# Sheet_1_2024-08-25.net
KiCad netlist of a schematic drawn in Altium Designer
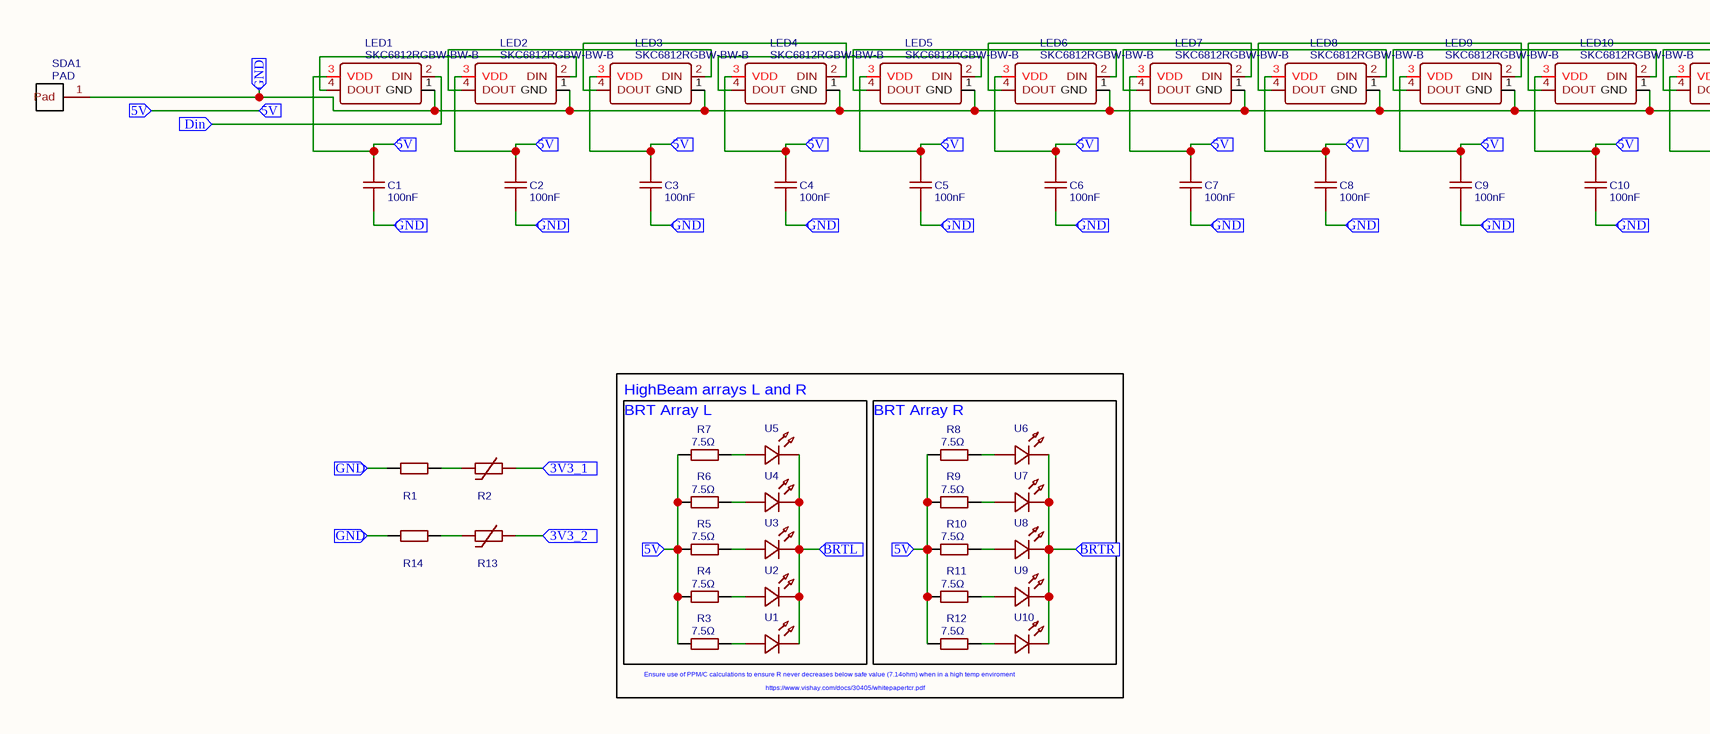
[diagram p0: Sheet_1_2024-08-25.schdoc, left]
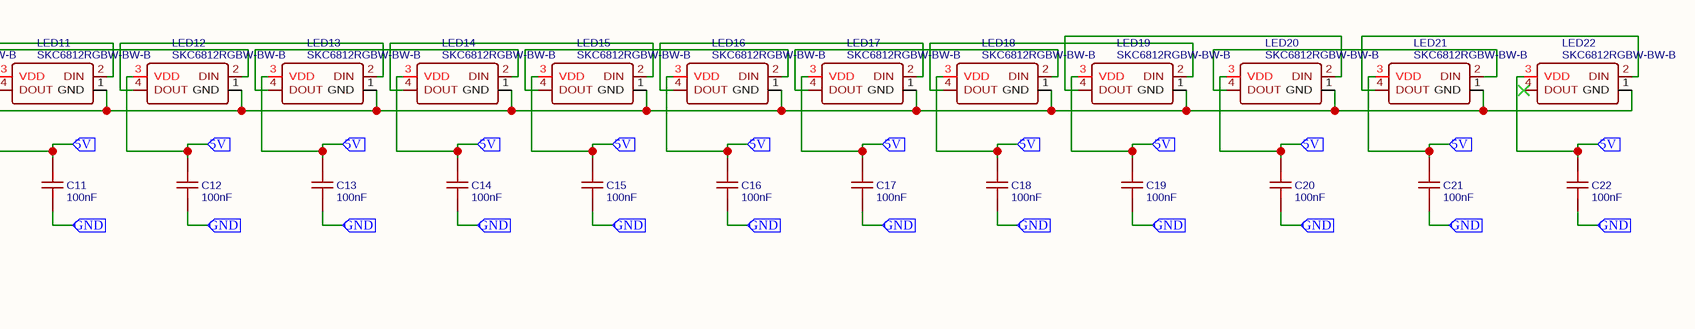
[diagram p1: Sheet_1_2024-08-25.schdoc, right]

(export (version "E")
  (design (tool "Eeschema 10.0.6"))
  (components
    (comp (ref "C1")
      (value "100nF")
      (fields
        (field (name "MANUFACTURER") "YAGEO(国巨)")
        (field (name "MANUFACTURER PART") "CC0402KRX7R6BB104")
        (field (name "CONTRIBUTOR") "LCSC")
      )
      (libsource (lib "altium-import") (part "root_0_100nF_"))
    )
    (comp (ref "C2")
      (value "100nF")
      (fields
        (field (name "MANUFACTURER") "YAGEO(国巨)")
        (field (name "MANUFACTURER PART") "CC0402KRX7R6BB104")
        (field (name "CONTRIBUTOR") "LCSC")
      )
      (libsource (lib "altium-import") (part "root_0_100nF_"))
    )
    (comp (ref "C3")
      (value "100nF")
      (fields
        (field (name "MANUFACTURER") "YAGEO(国巨)")
        (field (name "MANUFACTURER PART") "CC0402KRX7R6BB104")
        (field (name "CONTRIBUTOR") "LCSC")
      )
      (libsource (lib "altium-import") (part "root_0_100nF_"))
    )
    (comp (ref "C4")
      (value "100nF")
      (fields
        (field (name "MANUFACTURER") "YAGEO(国巨)")
        (field (name "MANUFACTURER PART") "CC0402KRX7R6BB104")
        (field (name "CONTRIBUTOR") "LCSC")
      )
      (libsource (lib "altium-import") (part "root_0_100nF_"))
    )
    (comp (ref "C5")
      (value "100nF")
      (fields
        (field (name "MANUFACTURER") "YAGEO(国巨)")
        (field (name "MANUFACTURER PART") "CC0402KRX7R6BB104")
        (field (name "CONTRIBUTOR") "LCSC")
      )
      (libsource (lib "altium-import") (part "root_0_100nF_"))
    )
    (comp (ref "C6")
      (value "100nF")
      (fields
        (field (name "MANUFACTURER") "YAGEO(国巨)")
        (field (name "MANUFACTURER PART") "CC0402KRX7R6BB104")
        (field (name "CONTRIBUTOR") "LCSC")
      )
      (libsource (lib "altium-import") (part "root_0_100nF_"))
    )
    (comp (ref "C7")
      (value "100nF")
      (fields
        (field (name "MANUFACTURER") "YAGEO(国巨)")
        (field (name "MANUFACTURER PART") "CC0402KRX7R6BB104")
        (field (name "CONTRIBUTOR") "LCSC")
      )
      (libsource (lib "altium-import") (part "root_0_100nF_"))
    )
    (comp (ref "C8")
      (value "100nF")
      (fields
        (field (name "MANUFACTURER") "YAGEO(国巨)")
        (field (name "MANUFACTURER PART") "CC0402KRX7R6BB104")
        (field (name "CONTRIBUTOR") "LCSC")
      )
      (libsource (lib "altium-import") (part "root_0_100nF_"))
    )
    (comp (ref "C9")
      (value "100nF")
      (fields
        (field (name "MANUFACTURER") "YAGEO(国巨)")
        (field (name "MANUFACTURER PART") "CC0402KRX7R6BB104")
        (field (name "CONTRIBUTOR") "LCSC")
      )
      (libsource (lib "altium-import") (part "root_0_100nF_"))
    )
    (comp (ref "C10")
      (value "100nF")
      (fields
        (field (name "MANUFACTURER") "YAGEO(国巨)")
        (field (name "MANUFACTURER PART") "CC0402KRX7R6BB104")
        (field (name "CONTRIBUTOR") "LCSC")
      )
      (libsource (lib "altium-import") (part "root_0_100nF_"))
    )
    (comp (ref "C11")
      (value "100nF")
      (fields
        (field (name "MANUFACTURER") "YAGEO(国巨)")
        (field (name "MANUFACTURER PART") "CC0402KRX7R6BB104")
        (field (name "CONTRIBUTOR") "LCSC")
      )
      (libsource (lib "altium-import") (part "root_0_100nF_"))
    )
    (comp (ref "C12")
      (value "100nF")
      (fields
        (field (name "MANUFACTURER") "YAGEO(国巨)")
        (field (name "MANUFACTURER PART") "CC0402KRX7R6BB104")
        (field (name "CONTRIBUTOR") "LCSC")
      )
      (libsource (lib "altium-import") (part "root_0_100nF_"))
    )
    (comp (ref "C13")
      (value "100nF")
      (fields
        (field (name "MANUFACTURER") "YAGEO(国巨)")
        (field (name "MANUFACTURER PART") "CC0402KRX7R6BB104")
        (field (name "CONTRIBUTOR") "LCSC")
      )
      (libsource (lib "altium-import") (part "root_0_100nF_"))
    )
    (comp (ref "C14")
      (value "100nF")
      (fields
        (field (name "MANUFACTURER") "YAGEO(国巨)")
        (field (name "MANUFACTURER PART") "CC0402KRX7R6BB104")
        (field (name "CONTRIBUTOR") "LCSC")
      )
      (libsource (lib "altium-import") (part "root_0_100nF_"))
    )
    (comp (ref "C15")
      (value "100nF")
      (fields
        (field (name "MANUFACTURER") "YAGEO(国巨)")
        (field (name "MANUFACTURER PART") "CC0402KRX7R6BB104")
        (field (name "CONTRIBUTOR") "LCSC")
      )
      (libsource (lib "altium-import") (part "root_0_100nF_"))
    )
    (comp (ref "C16")
      (value "100nF")
      (fields
        (field (name "MANUFACTURER") "YAGEO(国巨)")
        (field (name "MANUFACTURER PART") "CC0402KRX7R6BB104")
        (field (name "CONTRIBUTOR") "LCSC")
      )
      (libsource (lib "altium-import") (part "root_0_100nF_"))
    )
    (comp (ref "C17")
      (value "100nF")
      (fields
        (field (name "MANUFACTURER") "YAGEO(国巨)")
        (field (name "MANUFACTURER PART") "CC0402KRX7R6BB104")
        (field (name "CONTRIBUTOR") "LCSC")
      )
      (libsource (lib "altium-import") (part "root_0_100nF_"))
    )
    (comp (ref "C18")
      (value "100nF")
      (fields
        (field (name "MANUFACTURER") "YAGEO(国巨)")
        (field (name "MANUFACTURER PART") "CC0402KRX7R6BB104")
        (field (name "CONTRIBUTOR") "LCSC")
      )
      (libsource (lib "altium-import") (part "root_0_100nF_"))
    )
    (comp (ref "C19")
      (value "100nF")
      (fields
        (field (name "MANUFACTURER") "YAGEO(国巨)")
        (field (name "MANUFACTURER PART") "CC0402KRX7R6BB104")
        (field (name "CONTRIBUTOR") "LCSC")
      )
      (libsource (lib "altium-import") (part "root_0_100nF_"))
    )
    (comp (ref "C20")
      (value "100nF")
      (fields
        (field (name "MANUFACTURER") "YAGEO(国巨)")
        (field (name "MANUFACTURER PART") "CC0402KRX7R6BB104")
        (field (name "CONTRIBUTOR") "LCSC")
      )
      (libsource (lib "altium-import") (part "root_0_100nF_"))
    )
    (comp (ref "C21")
      (value "100nF")
      (fields
        (field (name "MANUFACTURER") "YAGEO(国巨)")
        (field (name "MANUFACTURER PART") "CC0402KRX7R6BB104")
        (field (name "CONTRIBUTOR") "LCSC")
      )
      (libsource (lib "altium-import") (part "root_0_100nF_"))
    )
    (comp (ref "C22")
      (value "100nF")
      (fields
        (field (name "MANUFACTURER") "YAGEO(国巨)")
        (field (name "MANUFACTURER PART") "CC0402KRX7R6BB104")
        (field (name "CONTRIBUTOR") "LCSC")
      )
      (libsource (lib "altium-import") (part "root_0_100nF_"))
    )
    (comp (ref "LED1")
      (value "SKC6812RGBW-BW-B")
      (fields (field (name "MANUFACTURER") "欧思科光电") (field (name "CONTRIBUTOR") "lcsc"))
      (libsource (lib "altium-import") (part "root_0_SKC6812RGBW-BW-B_"))
    )
    (comp (ref "LED2")
      (value "SKC6812RGBW-BW-B")
      (fields (field (name "MANUFACTURER") "欧思科光电") (field (name "CONTRIBUTOR") "lcsc"))
      (libsource (lib "altium-import") (part "root_0_SKC6812RGBW-BW-B_"))
    )
    (comp (ref "LED3")
      (value "SKC6812RGBW-BW-B")
      (fields (field (name "MANUFACTURER") "欧思科光电") (field (name "CONTRIBUTOR") "lcsc"))
      (libsource (lib "altium-import") (part "root_0_SKC6812RGBW-BW-B_"))
    )
    (comp (ref "LED4")
      (value "SKC6812RGBW-BW-B")
      (fields (field (name "MANUFACTURER") "欧思科光电") (field (name "CONTRIBUTOR") "lcsc"))
      (libsource (lib "altium-import") (part "root_0_SKC6812RGBW-BW-B_"))
    )
    (comp (ref "LED5")
      (value "SKC6812RGBW-BW-B")
      (fields (field (name "MANUFACTURER") "欧思科光电") (field (name "CONTRIBUTOR") "lcsc"))
      (libsource (lib "altium-import") (part "root_0_SKC6812RGBW-BW-B_"))
    )
    (comp (ref "LED6")
      (value "SKC6812RGBW-BW-B")
      (fields (field (name "MANUFACTURER") "欧思科光电") (field (name "CONTRIBUTOR") "lcsc"))
      (libsource (lib "altium-import") (part "root_0_SKC6812RGBW-BW-B_"))
    )
    (comp (ref "LED7")
      (value "SKC6812RGBW-BW-B")
      (fields (field (name "MANUFACTURER") "欧思科光电") (field (name "CONTRIBUTOR") "lcsc"))
      (libsource (lib "altium-import") (part "root_0_SKC6812RGBW-BW-B_"))
    )
    (comp (ref "LED8")
      (value "SKC6812RGBW-BW-B")
      (fields (field (name "MANUFACTURER") "欧思科光电") (field (name "CONTRIBUTOR") "lcsc"))
      (libsource (lib "altium-import") (part "root_0_SKC6812RGBW-BW-B_"))
    )
    (comp (ref "LED9")
      (value "SKC6812RGBW-BW-B")
      (fields (field (name "MANUFACTURER") "欧思科光电") (field (name "CONTRIBUTOR") "lcsc"))
      (libsource (lib "altium-import") (part "root_0_SKC6812RGBW-BW-B_"))
    )
    (comp (ref "LED10")
      (value "SKC6812RGBW-BW-B")
      (fields (field (name "MANUFACTURER") "欧思科光电") (field (name "CONTRIBUTOR") "lcsc"))
      (libsource (lib "altium-import") (part "root_0_SKC6812RGBW-BW-B_"))
    )
    (comp (ref "LED11")
      (value "SKC6812RGBW-BW-B")
      (fields (field (name "MANUFACTURER") "欧思科光电") (field (name "CONTRIBUTOR") "lcsc"))
      (libsource (lib "altium-import") (part "root_0_SKC6812RGBW-BW-B_"))
    )
    (comp (ref "LED12")
      (value "SKC6812RGBW-BW-B")
      (fields (field (name "MANUFACTURER") "欧思科光电") (field (name "CONTRIBUTOR") "lcsc"))
      (libsource (lib "altium-import") (part "root_0_SKC6812RGBW-BW-B_"))
    )
    (comp (ref "LED13")
      (value "SKC6812RGBW-BW-B")
      (fields (field (name "MANUFACTURER") "欧思科光电") (field (name "CONTRIBUTOR") "lcsc"))
      (libsource (lib "altium-import") (part "root_0_SKC6812RGBW-BW-B_"))
    )
    (comp (ref "LED14")
      (value "SKC6812RGBW-BW-B")
      (fields (field (name "MANUFACTURER") "欧思科光电") (field (name "CONTRIBUTOR") "lcsc"))
      (libsource (lib "altium-import") (part "root_0_SKC6812RGBW-BW-B_"))
    )
    (comp (ref "LED15")
      (value "SKC6812RGBW-BW-B")
      (fields (field (name "MANUFACTURER") "欧思科光电") (field (name "CONTRIBUTOR") "lcsc"))
      (libsource (lib "altium-import") (part "root_0_SKC6812RGBW-BW-B_"))
    )
    (comp (ref "LED16")
      (value "SKC6812RGBW-BW-B")
      (fields (field (name "MANUFACTURER") "欧思科光电") (field (name "CONTRIBUTOR") "lcsc"))
      (libsource (lib "altium-import") (part "root_0_SKC6812RGBW-BW-B_"))
    )
    (comp (ref "LED17")
      (value "SKC6812RGBW-BW-B")
      (fields (field (name "MANUFACTURER") "欧思科光电") (field (name "CONTRIBUTOR") "lcsc"))
      (libsource (lib "altium-import") (part "root_0_SKC6812RGBW-BW-B_"))
    )
    (comp (ref "LED18")
      (value "SKC6812RGBW-BW-B")
      (fields (field (name "MANUFACTURER") "欧思科光电") (field (name "CONTRIBUTOR") "lcsc"))
      (libsource (lib "altium-import") (part "root_0_SKC6812RGBW-BW-B_"))
    )
    (comp (ref "LED19")
      (value "SKC6812RGBW-BW-B")
      (fields (field (name "MANUFACTURER") "欧思科光电") (field (name "CONTRIBUTOR") "lcsc"))
      (libsource (lib "altium-import") (part "root_0_SKC6812RGBW-BW-B_"))
    )
    (comp (ref "LED20")
      (value "SKC6812RGBW-BW-B")
      (fields (field (name "MANUFACTURER") "欧思科光电") (field (name "CONTRIBUTOR") "lcsc"))
      (libsource (lib "altium-import") (part "root_0_SKC6812RGBW-BW-B_"))
    )
    (comp (ref "LED21")
      (value "SKC6812RGBW-BW-B")
      (fields (field (name "MANUFACTURER") "欧思科光电") (field (name "CONTRIBUTOR") "lcsc"))
      (libsource (lib "altium-import") (part "root_0_SKC6812RGBW-BW-B_"))
    )
    (comp (ref "LED22")
      (value "SKC6812RGBW-BW-B")
      (fields (field (name "MANUFACTURER") "欧思科光电") (field (name "CONTRIBUTOR") "lcsc"))
      (libsource (lib "altium-import") (part "root_0_SKC6812RGBW-BW-B_"))
    )
    (comp (ref "R1")
      (value "100kΩ")
      (fields
        (field (name "MANUFACTURER") "UNI-ROYAL(厚声)")
        (field (name "MANUFACTURER PART") "0603WAF1003T5E")
      )
      (libsource (lib "altium-import") (part "root_0_100kΩ_"))
    )
    (comp (ref "R2")
      (value "SDNT1608X104F3950FTF")
      (fields (field (name "MANUFACTURER") "Sunlord(顺络)") (field (name "CONTRIBUTOR") "lcsc"))
      (libsource (lib "altium-import") (part "root_0_SDNT1608X104F3950FTF_"))
    )
    (comp (ref "R3")
      (value "7.5Ω")
      (fields
        (field (name "MANUFACTURER") "UNI-ROYAL(厚声)")
        (field (name "MANUFACTURER PART") "25121WF750KT4E")
      )
      (libsource (lib "altium-import") (part "root_0_7.5Ω_"))
    )
    (comp (ref "R4")
      (value "7.5Ω")
      (fields
        (field (name "MANUFACTURER") "UNI-ROYAL(厚声)")
        (field (name "MANUFACTURER PART") "25121WF750KT4E")
      )
      (libsource (lib "altium-import") (part "root_0_7.5Ω_"))
    )
    (comp (ref "R5")
      (value "7.5Ω")
      (fields
        (field (name "MANUFACTURER") "UNI-ROYAL(厚声)")
        (field (name "MANUFACTURER PART") "25121WF750KT4E")
      )
      (libsource (lib "altium-import") (part "root_0_7.5Ω_"))
    )
    (comp (ref "R6")
      (value "7.5Ω")
      (fields
        (field (name "MANUFACTURER") "UNI-ROYAL(厚声)")
        (field (name "MANUFACTURER PART") "25121WF750KT4E")
      )
      (libsource (lib "altium-import") (part "root_0_7.5Ω_"))
    )
    (comp (ref "R7")
      (value "7.5Ω")
      (fields
        (field (name "MANUFACTURER") "UNI-ROYAL(厚声)")
        (field (name "MANUFACTURER PART") "25121WF750KT4E")
      )
      (libsource (lib "altium-import") (part "root_0_7.5Ω_"))
    )
    (comp (ref "R8")
      (value "7.5Ω")
      (fields
        (field (name "MANUFACTURER") "UNI-ROYAL(厚声)")
        (field (name "MANUFACTURER PART") "25121WF750KT4E")
      )
      (libsource (lib "altium-import") (part "root_0_7.5Ω_"))
    )
    (comp (ref "R9")
      (value "7.5Ω")
      (fields
        (field (name "MANUFACTURER") "UNI-ROYAL(厚声)")
        (field (name "MANUFACTURER PART") "25121WF750KT4E")
      )
      (libsource (lib "altium-import") (part "root_0_7.5Ω_"))
    )
    (comp (ref "R10")
      (value "7.5Ω")
      (fields
        (field (name "MANUFACTURER") "UNI-ROYAL(厚声)")
        (field (name "MANUFACTURER PART") "25121WF750KT4E")
      )
      (libsource (lib "altium-import") (part "root_0_7.5Ω_"))
    )
    (comp (ref "R11")
      (value "7.5Ω")
      (fields
        (field (name "MANUFACTURER") "UNI-ROYAL(厚声)")
        (field (name "MANUFACTURER PART") "25121WF750KT4E")
      )
      (libsource (lib "altium-import") (part "root_0_7.5Ω_"))
    )
    (comp (ref "R12")
      (value "7.5Ω")
      (fields
        (field (name "MANUFACTURER") "UNI-ROYAL(厚声)")
        (field (name "MANUFACTURER PART") "25121WF750KT4E")
      )
      (libsource (lib "altium-import") (part "root_0_7.5Ω_"))
    )
    (comp (ref "R13")
      (value "SDNT1608X104F3950FTF")
      (fields (field (name "MANUFACTURER") "Sunlord(顺络)") (field (name "CONTRIBUTOR") "lcsc"))
      (libsource (lib "altium-import") (part "root_0_SDNT1608X104F3950FTF_"))
    )
    (comp (ref "R14")
      (value "100kΩ")
      (fields
        (field (name "MANUFACTURER") "UNI-ROYAL(厚声)")
        (field (name "MANUFACTURER PART") "0603WAF1003T5E")
      )
      (libsource (lib "altium-import") (part "root_0_100kΩ_"))
    )
    (comp (ref "SDA1")
      (value "PAD")
      (fields (field (name "CONTRIBUTOR") "edwardkeate"))
      (libsource (lib "altium-import") (part "root_0_PAD_"))
    )
    (comp (ref "U1")
      (value "JNJ-LTJH0111W60/26MIL/8000-9000K")
      (fields
        (field (name "MANUFACTURER") "JNJ OPTOELECTRONICS(强生光电)")
        (field (name "MANUFACTURER PART") "JNJ-LTJH0111W60/26mil/8000-9000K")
        (field (name "CONTRIBUTOR") "lcsc")
      )
      (libsource (lib "altium-import") (part "root_0_JNJ-LTJH0111W60/26MIL/8000-9000K_"))
    )
    (comp (ref "U2")
      (value "JNJ-LTJH0111W60/26MIL/8000-9000K")
      (fields
        (field (name "MANUFACTURER") "JNJ OPTOELECTRONICS(强生光电)")
        (field (name "MANUFACTURER PART") "JNJ-LTJH0111W60/26mil/8000-9000K")
        (field (name "CONTRIBUTOR") "lcsc")
      )
      (libsource (lib "altium-import") (part "root_0_JNJ-LTJH0111W60/26MIL/8000-9000K_"))
    )
    (comp (ref "U3")
      (value "JNJ-LTJH0111W60/26MIL/8000-9000K")
      (fields
        (field (name "MANUFACTURER") "JNJ OPTOELECTRONICS(强生光电)")
        (field (name "MANUFACTURER PART") "JNJ-LTJH0111W60/26mil/8000-9000K")
        (field (name "CONTRIBUTOR") "lcsc")
      )
      (libsource (lib "altium-import") (part "root_0_JNJ-LTJH0111W60/26MIL/8000-9000K_"))
    )
    (comp (ref "U4")
      (value "JNJ-LTJH0111W60/26MIL/8000-9000K")
      (fields
        (field (name "MANUFACTURER") "JNJ OPTOELECTRONICS(强生光电)")
        (field (name "MANUFACTURER PART") "JNJ-LTJH0111W60/26mil/8000-9000K")
        (field (name "CONTRIBUTOR") "lcsc")
      )
      (libsource (lib "altium-import") (part "root_0_JNJ-LTJH0111W60/26MIL/8000-9000K_"))
    )
    (comp (ref "U5")
      (value "JNJ-LTJH0111W60/26MIL/8000-9000K")
      (fields
        (field (name "MANUFACTURER") "JNJ OPTOELECTRONICS(强生光电)")
        (field (name "MANUFACTURER PART") "JNJ-LTJH0111W60/26mil/8000-9000K")
        (field (name "CONTRIBUTOR") "lcsc")
      )
      (libsource (lib "altium-import") (part "root_0_JNJ-LTJH0111W60/26MIL/8000-9000K_"))
    )
    (comp (ref "U6")
      (value "JNJ-LTJH0111W60/26MIL/8000-9000K")
      (fields
        (field (name "MANUFACTURER") "JNJ OPTOELECTRONICS(强生光电)")
        (field (name "MANUFACTURER PART") "JNJ-LTJH0111W60/26mil/8000-9000K")
        (field (name "CONTRIBUTOR") "lcsc")
      )
      (libsource (lib "altium-import") (part "root_0_JNJ-LTJH0111W60/26MIL/8000-9000K_"))
    )
    (comp (ref "U7")
      (value "JNJ-LTJH0111W60/26MIL/8000-9000K")
      (fields
        (field (name "MANUFACTURER") "JNJ OPTOELECTRONICS(强生光电)")
        (field (name "MANUFACTURER PART") "JNJ-LTJH0111W60/26mil/8000-9000K")
        (field (name "CONTRIBUTOR") "lcsc")
      )
      (libsource (lib "altium-import") (part "root_0_JNJ-LTJH0111W60/26MIL/8000-9000K_"))
    )
    (comp (ref "U8")
      (value "JNJ-LTJH0111W60/26MIL/8000-9000K")
      (fields
        (field (name "MANUFACTURER") "JNJ OPTOELECTRONICS(强生光电)")
        (field (name "MANUFACTURER PART") "JNJ-LTJH0111W60/26mil/8000-9000K")
        (field (name "CONTRIBUTOR") "lcsc")
      )
      (libsource (lib "altium-import") (part "root_0_JNJ-LTJH0111W60/26MIL/8000-9000K_"))
    )
    (comp (ref "U9")
      (value "JNJ-LTJH0111W60/26MIL/8000-9000K")
      (fields
        (field (name "MANUFACTURER") "JNJ OPTOELECTRONICS(强生光电)")
        (field (name "MANUFACTURER PART") "JNJ-LTJH0111W60/26mil/8000-9000K")
        (field (name "CONTRIBUTOR") "lcsc")
      )
      (libsource (lib "altium-import") (part "root_0_JNJ-LTJH0111W60/26MIL/8000-9000K_"))
    )
    (comp (ref "U10")
      (value "JNJ-LTJH0111W60/26MIL/8000-9000K")
      (fields
        (field (name "MANUFACTURER") "JNJ OPTOELECTRONICS(强生光电)")
        (field (name "MANUFACTURER PART") "JNJ-LTJH0111W60/26mil/8000-9000K")
        (field (name "CONTRIBUTOR") "lcsc")
      )
      (libsource (lib "altium-import") (part "root_0_JNJ-LTJH0111W60/26MIL/8000-9000K_"))
    )
  )
  (nets
    (net (code "1") (name "/3V3_1") (class "Default")
      (node (ref "R2") (pin "2") (pinfunction "2_2") (pintype "passive"))
    )
    (net (code "2") (name "/3V3_2") (class "Default")
      (node (ref "R13") (pin "2") (pinfunction "2_2") (pintype "passive"))
    )
    (net (code "3") (name "/5V") (class "Default")
      (node (ref "C1") (pin "2") (pinfunction "2_2") (pintype "passive"))
      (node (ref "C10") (pin "2") (pinfunction "2_2") (pintype "passive"))
      (node (ref "C11") (pin "2") (pinfunction "2_2") (pintype "passive"))
      (node (ref "C12") (pin "2") (pinfunction "2_2") (pintype "passive"))
      (node (ref "C13") (pin "2") (pinfunction "2_2") (pintype "passive"))
      (node (ref "C14") (pin "2") (pinfunction "2_2") (pintype "passive"))
      (node (ref "C15") (pin "2") (pinfunction "2_2") (pintype "passive"))
      (node (ref "C16") (pin "2") (pinfunction "2_2") (pintype "passive"))
      (node (ref "C17") (pin "2") (pinfunction "2_2") (pintype "passive"))
      (node (ref "C18") (pin "2") (pinfunction "2_2") (pintype "passive"))
      (node (ref "C19") (pin "2") (pinfunction "2_2") (pintype "passive"))
      (node (ref "C2") (pin "2") (pinfunction "2_2") (pintype "passive"))
      (node (ref "C20") (pin "2") (pinfunction "2_2") (pintype "passive"))
      (node (ref "C21") (pin "2") (pinfunction "2_2") (pintype "passive"))
      (node (ref "C22") (pin "2") (pinfunction "2_2") (pintype "passive"))
      (node (ref "C3") (pin "2") (pinfunction "2_2") (pintype "passive"))
      (node (ref "C4") (pin "2") (pinfunction "2_2") (pintype "passive"))
      (node (ref "C5") (pin "2") (pinfunction "2_2") (pintype "passive"))
      (node (ref "C6") (pin "2") (pinfunction "2_2") (pintype "passive"))
      (node (ref "C7") (pin "2") (pinfunction "2_2") (pintype "passive"))
      (node (ref "C8") (pin "2") (pinfunction "2_2") (pintype "passive"))
      (node (ref "C9") (pin "2") (pinfunction "2_2") (pintype "passive"))
      (node (ref "LED1") (pin "3") (pinfunction "VDD_3") (pintype "passive"))
      (node (ref "LED10") (pin "3") (pinfunction "VDD_3") (pintype "passive"))
      (node (ref "LED11") (pin "3") (pinfunction "VDD_3") (pintype "passive"))
      (node (ref "LED12") (pin "3") (pinfunction "VDD_3") (pintype "passive"))
      (node (ref "LED13") (pin "3") (pinfunction "VDD_3") (pintype "passive"))
      (node (ref "LED14") (pin "3") (pinfunction "VDD_3") (pintype "passive"))
      (node (ref "LED15") (pin "3") (pinfunction "VDD_3") (pintype "passive"))
      (node (ref "LED16") (pin "3") (pinfunction "VDD_3") (pintype "passive"))
      (node (ref "LED17") (pin "3") (pinfunction "VDD_3") (pintype "passive"))
      (node (ref "LED18") (pin "3") (pinfunction "VDD_3") (pintype "passive"))
      (node (ref "LED19") (pin "3") (pinfunction "VDD_3") (pintype "passive"))
      (node (ref "LED2") (pin "3") (pinfunction "VDD_3") (pintype "passive"))
      (node (ref "LED20") (pin "3") (pinfunction "VDD_3") (pintype "passive"))
      (node (ref "LED21") (pin "3") (pinfunction "VDD_3") (pintype "passive"))
      (node (ref "LED22") (pin "3") (pinfunction "VDD_3") (pintype "passive"))
      (node (ref "LED3") (pin "3") (pinfunction "VDD_3") (pintype "passive"))
      (node (ref "LED4") (pin "3") (pinfunction "VDD_3") (pintype "passive"))
      (node (ref "LED5") (pin "3") (pinfunction "VDD_3") (pintype "passive"))
      (node (ref "LED6") (pin "3") (pinfunction "VDD_3") (pintype "passive"))
      (node (ref "LED7") (pin "3") (pinfunction "VDD_3") (pintype "passive"))
      (node (ref "LED8") (pin "3") (pinfunction "VDD_3") (pintype "passive"))
      (node (ref "LED9") (pin "3") (pinfunction "VDD_3") (pintype "passive"))
      (node (ref "R10") (pin "1") (pinfunction "1_1") (pintype "passive"))
      (node (ref "R11") (pin "1") (pinfunction "1_1") (pintype "passive"))
      (node (ref "R12") (pin "1") (pinfunction "1_1") (pintype "passive"))
      (node (ref "R3") (pin "1") (pinfunction "1_1") (pintype "passive"))
      (node (ref "R4") (pin "1") (pinfunction "1_1") (pintype "passive"))
      (node (ref "R5") (pin "1") (pinfunction "1_1") (pintype "passive"))
      (node (ref "R6") (pin "1") (pinfunction "1_1") (pintype "passive"))
      (node (ref "R7") (pin "1") (pinfunction "1_1") (pintype "passive"))
      (node (ref "R8") (pin "1") (pinfunction "1_1") (pintype "passive"))
      (node (ref "R9") (pin "1") (pinfunction "1_1") (pintype "passive"))
    )
    (net (code "4") (name "/BRTL") (class "Default")
      (node (ref "U1") (pin "2") (pinfunction "K_2") (pintype "passive"))
      (node (ref "U2") (pin "2") (pinfunction "K_2") (pintype "passive"))
      (node (ref "U3") (pin "2") (pinfunction "K_2") (pintype "passive"))
      (node (ref "U4") (pin "2") (pinfunction "K_2") (pintype "passive"))
      (node (ref "U5") (pin "2") (pinfunction "K_2") (pintype "passive"))
    )
    (net (code "5") (name "/BRTR") (class "Default")
      (node (ref "U10") (pin "2") (pinfunction "K_2") (pintype "passive"))
      (node (ref "U6") (pin "2") (pinfunction "K_2") (pintype "passive"))
      (node (ref "U7") (pin "2") (pinfunction "K_2") (pintype "passive"))
      (node (ref "U8") (pin "2") (pinfunction "K_2") (pintype "passive"))
      (node (ref "U9") (pin "2") (pinfunction "K_2") (pintype "passive"))
    )
    (net (code "6") (name "/Din") (class "Default")
      (node (ref "LED1") (pin "2") (pinfunction "DIN_2") (pintype "passive"))
    )
    (net (code "7") (name "/GND") (class "Default")
      (node (ref "C1") (pin "1") (pinfunction "1_1") (pintype "passive"))
      (node (ref "C10") (pin "1") (pinfunction "1_1") (pintype "passive"))
      (node (ref "C11") (pin "1") (pinfunction "1_1") (pintype "passive"))
      (node (ref "C12") (pin "1") (pinfunction "1_1") (pintype "passive"))
      (node (ref "C13") (pin "1") (pinfunction "1_1") (pintype "passive"))
      (node (ref "C14") (pin "1") (pinfunction "1_1") (pintype "passive"))
      (node (ref "C15") (pin "1") (pinfunction "1_1") (pintype "passive"))
      (node (ref "C16") (pin "1") (pinfunction "1_1") (pintype "passive"))
      (node (ref "C17") (pin "1") (pinfunction "1_1") (pintype "passive"))
      (node (ref "C18") (pin "1") (pinfunction "1_1") (pintype "passive"))
      (node (ref "C19") (pin "1") (pinfunction "1_1") (pintype "passive"))
      (node (ref "C2") (pin "1") (pinfunction "1_1") (pintype "passive"))
      (node (ref "C20") (pin "1") (pinfunction "1_1") (pintype "passive"))
      (node (ref "C21") (pin "1") (pinfunction "1_1") (pintype "passive"))
      (node (ref "C22") (pin "1") (pinfunction "1_1") (pintype "passive"))
      (node (ref "C3") (pin "1") (pinfunction "1_1") (pintype "passive"))
      (node (ref "C4") (pin "1") (pinfunction "1_1") (pintype "passive"))
      (node (ref "C5") (pin "1") (pinfunction "1_1") (pintype "passive"))
      (node (ref "C6") (pin "1") (pinfunction "1_1") (pintype "passive"))
      (node (ref "C7") (pin "1") (pinfunction "1_1") (pintype "passive"))
      (node (ref "C8") (pin "1") (pinfunction "1_1") (pintype "passive"))
      (node (ref "C9") (pin "1") (pinfunction "1_1") (pintype "passive"))
      (node (ref "LED1") (pin "1") (pinfunction "GND_1") (pintype "passive"))
      (node (ref "LED10") (pin "1") (pinfunction "GND_1") (pintype "passive"))
      (node (ref "LED11") (pin "1") (pinfunction "GND_1") (pintype "passive"))
      (node (ref "LED12") (pin "1") (pinfunction "GND_1") (pintype "passive"))
      (node (ref "LED13") (pin "1") (pinfunction "GND_1") (pintype "passive"))
      (node (ref "LED14") (pin "1") (pinfunction "GND_1") (pintype "passive"))
      (node (ref "LED15") (pin "1") (pinfunction "GND_1") (pintype "passive"))
      (node (ref "LED16") (pin "1") (pinfunction "GND_1") (pintype "passive"))
      (node (ref "LED17") (pin "1") (pinfunction "GND_1") (pintype "passive"))
      (node (ref "LED18") (pin "1") (pinfunction "GND_1") (pintype "passive"))
      (node (ref "LED19") (pin "1") (pinfunction "GND_1") (pintype "passive"))
      (node (ref "LED2") (pin "1") (pinfunction "GND_1") (pintype "passive"))
      (node (ref "LED20") (pin "1") (pinfunction "GND_1") (pintype "passive"))
      (node (ref "LED21") (pin "1") (pinfunction "GND_1") (pintype "passive"))
      (node (ref "LED22") (pin "1") (pinfunction "GND_1") (pintype "passive"))
      (node (ref "LED3") (pin "1") (pinfunction "GND_1") (pintype "passive"))
      (node (ref "LED4") (pin "1") (pinfunction "GND_1") (pintype "passive"))
      (node (ref "LED5") (pin "1") (pinfunction "GND_1") (pintype "passive"))
      (node (ref "LED6") (pin "1") (pinfunction "GND_1") (pintype "passive"))
      (node (ref "LED7") (pin "1") (pinfunction "GND_1") (pintype "passive"))
      (node (ref "LED8") (pin "1") (pinfunction "GND_1") (pintype "passive"))
      (node (ref "LED9") (pin "1") (pinfunction "GND_1") (pintype "passive"))
      (node (ref "R1") (pin "1") (pinfunction "1_1") (pintype "passive"))
      (node (ref "R14") (pin "1") (pinfunction "1_1") (pintype "passive"))
      (node (ref "SDA1") (pin "1") (pinfunction "Pad_1") (pintype "passive"))
    )
    (net (code "8") (name "Net-(LED1-DOUT)") (class "Default")
      (node (ref "LED1") (pin "4") (pinfunction "DOUT_4") (pintype "passive"))
      (node (ref "LED2") (pin "2") (pinfunction "DIN_2") (pintype "passive"))
    )
    (net (code "9") (name "Net-(LED2-DOUT)") (class "Default")
      (node (ref "LED2") (pin "4") (pinfunction "DOUT_4") (pintype "passive"))
      (node (ref "LED3") (pin "2") (pinfunction "DIN_2") (pintype "passive"))
    )
    (net (code "10") (name "Net-(LED3-DOUT)") (class "Default")
      (node (ref "LED3") (pin "4") (pinfunction "DOUT_4") (pintype "passive"))
      (node (ref "LED4") (pin "2") (pinfunction "DIN_2") (pintype "passive"))
    )
    (net (code "11") (name "Net-(LED4-DOUT)") (class "Default")
      (node (ref "LED4") (pin "4") (pinfunction "DOUT_4") (pintype "passive"))
      (node (ref "LED5") (pin "2") (pinfunction "DIN_2") (pintype "passive"))
    )
    (net (code "12") (name "Net-(LED5-DOUT)") (class "Default")
      (node (ref "LED5") (pin "4") (pinfunction "DOUT_4") (pintype "passive"))
      (node (ref "LED6") (pin "2") (pinfunction "DIN_2") (pintype "passive"))
    )
    (net (code "13") (name "Net-(LED6-DOUT)") (class "Default")
      (node (ref "LED6") (pin "4") (pinfunction "DOUT_4") (pintype "passive"))
      (node (ref "LED7") (pin "2") (pinfunction "DIN_2") (pintype "passive"))
    )
    (net (code "14") (name "Net-(LED7-DOUT)") (class "Default")
      (node (ref "LED7") (pin "4") (pinfunction "DOUT_4") (pintype "passive"))
      (node (ref "LED8") (pin "2") (pinfunction "DIN_2") (pintype "passive"))
    )
    (net (code "15") (name "Net-(LED8-DOUT)") (class "Default")
      (node (ref "LED8") (pin "4") (pinfunction "DOUT_4") (pintype "passive"))
      (node (ref "LED9") (pin "2") (pinfunction "DIN_2") (pintype "passive"))
    )
    (net (code "16") (name "Net-(LED10-DIN)") (class "Default")
      (node (ref "LED10") (pin "2") (pinfunction "DIN_2") (pintype "passive"))
      (node (ref "LED9") (pin "4") (pinfunction "DOUT_4") (pintype "passive"))
    )
    (net (code "17") (name "Net-(LED10-DOUT)") (class "Default")
      (node (ref "LED10") (pin "4") (pinfunction "DOUT_4") (pintype "passive"))
      (node (ref "LED11") (pin "2") (pinfunction "DIN_2") (pintype "passive"))
    )
    (net (code "18") (name "Net-(LED11-DOUT)") (class "Default")
      (node (ref "LED11") (pin "4") (pinfunction "DOUT_4") (pintype "passive"))
      (node (ref "LED12") (pin "2") (pinfunction "DIN_2") (pintype "passive"))
    )
    (net (code "19") (name "Net-(LED12-DOUT)") (class "Default")
      (node (ref "LED12") (pin "4") (pinfunction "DOUT_4") (pintype "passive"))
      (node (ref "LED13") (pin "2") (pinfunction "DIN_2") (pintype "passive"))
    )
    (net (code "20") (name "Net-(LED13-DOUT)") (class "Default")
      (node (ref "LED13") (pin "4") (pinfunction "DOUT_4") (pintype "passive"))
      (node (ref "LED14") (pin "2") (pinfunction "DIN_2") (pintype "passive"))
    )
    (net (code "21") (name "Net-(LED14-DOUT)") (class "Default")
      (node (ref "LED14") (pin "4") (pinfunction "DOUT_4") (pintype "passive"))
      (node (ref "LED15") (pin "2") (pinfunction "DIN_2") (pintype "passive"))
    )
    (net (code "22") (name "Net-(LED15-DOUT)") (class "Default")
      (node (ref "LED15") (pin "4") (pinfunction "DOUT_4") (pintype "passive"))
      (node (ref "LED16") (pin "2") (pinfunction "DIN_2") (pintype "passive"))
    )
    (net (code "23") (name "Net-(LED16-DOUT)") (class "Default")
      (node (ref "LED16") (pin "4") (pinfunction "DOUT_4") (pintype "passive"))
      (node (ref "LED17") (pin "2") (pinfunction "DIN_2") (pintype "passive"))
    )
    (net (code "24") (name "Net-(LED17-DOUT)") (class "Default")
      (node (ref "LED17") (pin "4") (pinfunction "DOUT_4") (pintype "passive"))
      (node (ref "LED18") (pin "2") (pinfunction "DIN_2") (pintype "passive"))
    )
    (net (code "25") (name "Net-(LED18-DOUT)") (class "Default")
      (node (ref "LED18") (pin "4") (pinfunction "DOUT_4") (pintype "passive"))
      (node (ref "LED19") (pin "2") (pinfunction "DIN_2") (pintype "passive"))
    )
    (net (code "26") (name "Net-(LED19-DOUT)") (class "Default")
      (node (ref "LED19") (pin "4") (pinfunction "DOUT_4") (pintype "passive"))
      (node (ref "LED20") (pin "2") (pinfunction "DIN_2") (pintype "passive"))
    )
    (net (code "27") (name "Net-(LED20-DOUT)") (class "Default")
      (node (ref "LED20") (pin "4") (pinfunction "DOUT_4") (pintype "passive"))
      (node (ref "LED21") (pin "2") (pinfunction "DIN_2") (pintype "passive"))
    )
    (net (code "28") (name "Net-(LED21-DOUT)") (class "Default")
      (node (ref "LED21") (pin "4") (pinfunction "DOUT_4") (pintype "passive"))
      (node (ref "LED22") (pin "2") (pinfunction "DIN_2") (pintype "passive"))
    )
    (net (code "29") (name "Net-(R1-Pad2)") (class "Default")
      (node (ref "R1") (pin "2") (pinfunction "2_2") (pintype "passive"))
      (node (ref "R2") (pin "1") (pinfunction "1_1") (pintype "passive"))
    )
    (net (code "30") (name "Net-(R13-Pad1)") (class "Default")
      (node (ref "R13") (pin "1") (pinfunction "1_1") (pintype "passive"))
      (node (ref "R14") (pin "2") (pinfunction "2_2") (pintype "passive"))
    )
    (net (code "31") (name "Net-(U1-A)") (class "Default")
      (node (ref "R3") (pin "2") (pinfunction "2_2") (pintype "passive"))
      (node (ref "U1") (pin "1") (pinfunction "A_1") (pintype "passive"))
    )
    (net (code "32") (name "Net-(U2-A)") (class "Default")
      (node (ref "R4") (pin "2") (pinfunction "2_2") (pintype "passive"))
      (node (ref "U2") (pin "1") (pinfunction "A_1") (pintype "passive"))
    )
    (net (code "33") (name "Net-(U3-A)") (class "Default")
      (node (ref "R5") (pin "2") (pinfunction "2_2") (pintype "passive"))
      (node (ref "U3") (pin "1") (pinfunction "A_1") (pintype "passive"))
    )
    (net (code "34") (name "Net-(U4-A)") (class "Default")
      (node (ref "R6") (pin "2") (pinfunction "2_2") (pintype "passive"))
      (node (ref "U4") (pin "1") (pinfunction "A_1") (pintype "passive"))
    )
    (net (code "35") (name "Net-(U5-A)") (class "Default")
      (node (ref "R7") (pin "2") (pinfunction "2_2") (pintype "passive"))
      (node (ref "U5") (pin "1") (pinfunction "A_1") (pintype "passive"))
    )
    (net (code "36") (name "Net-(U6-A)") (class "Default")
      (node (ref "R8") (pin "2") (pinfunction "2_2") (pintype "passive"))
      (node (ref "U6") (pin "1") (pinfunction "A_1") (pintype "passive"))
    )
    (net (code "37") (name "Net-(U7-A)") (class "Default")
      (node (ref "R9") (pin "2") (pinfunction "2_2") (pintype "passive"))
      (node (ref "U7") (pin "1") (pinfunction "A_1") (pintype "passive"))
    )
    (net (code "38") (name "Net-(U8-A)") (class "Default")
      (node (ref "R10") (pin "2") (pinfunction "2_2") (pintype "passive"))
      (node (ref "U8") (pin "1") (pinfunction "A_1") (pintype "passive"))
    )
    (net (code "39") (name "Net-(U9-A)") (class "Default")
      (node (ref "R11") (pin "2") (pinfunction "2_2") (pintype "passive"))
      (node (ref "U9") (pin "1") (pinfunction "A_1") (pintype "passive"))
    )
    (net (code "40") (name "Net-(U10-A)") (class "Default")
      (node (ref "R12") (pin "2") (pinfunction "2_2") (pintype "passive"))
      (node (ref "U10") (pin "1") (pinfunction "A_1") (pintype "passive"))
    )
    (net (code "41") (name "unconnected-(LED22-DOUT-Pad4)") (class "Default")
      (node (ref "LED22") (pin "4") (pinfunction "DOUT_4") (pintype "passive+no_connect"))
    )
  )
)
